# 04_iMX_8X_PWR.net
KiCad netlist of a schematic drawn in Altium Designer
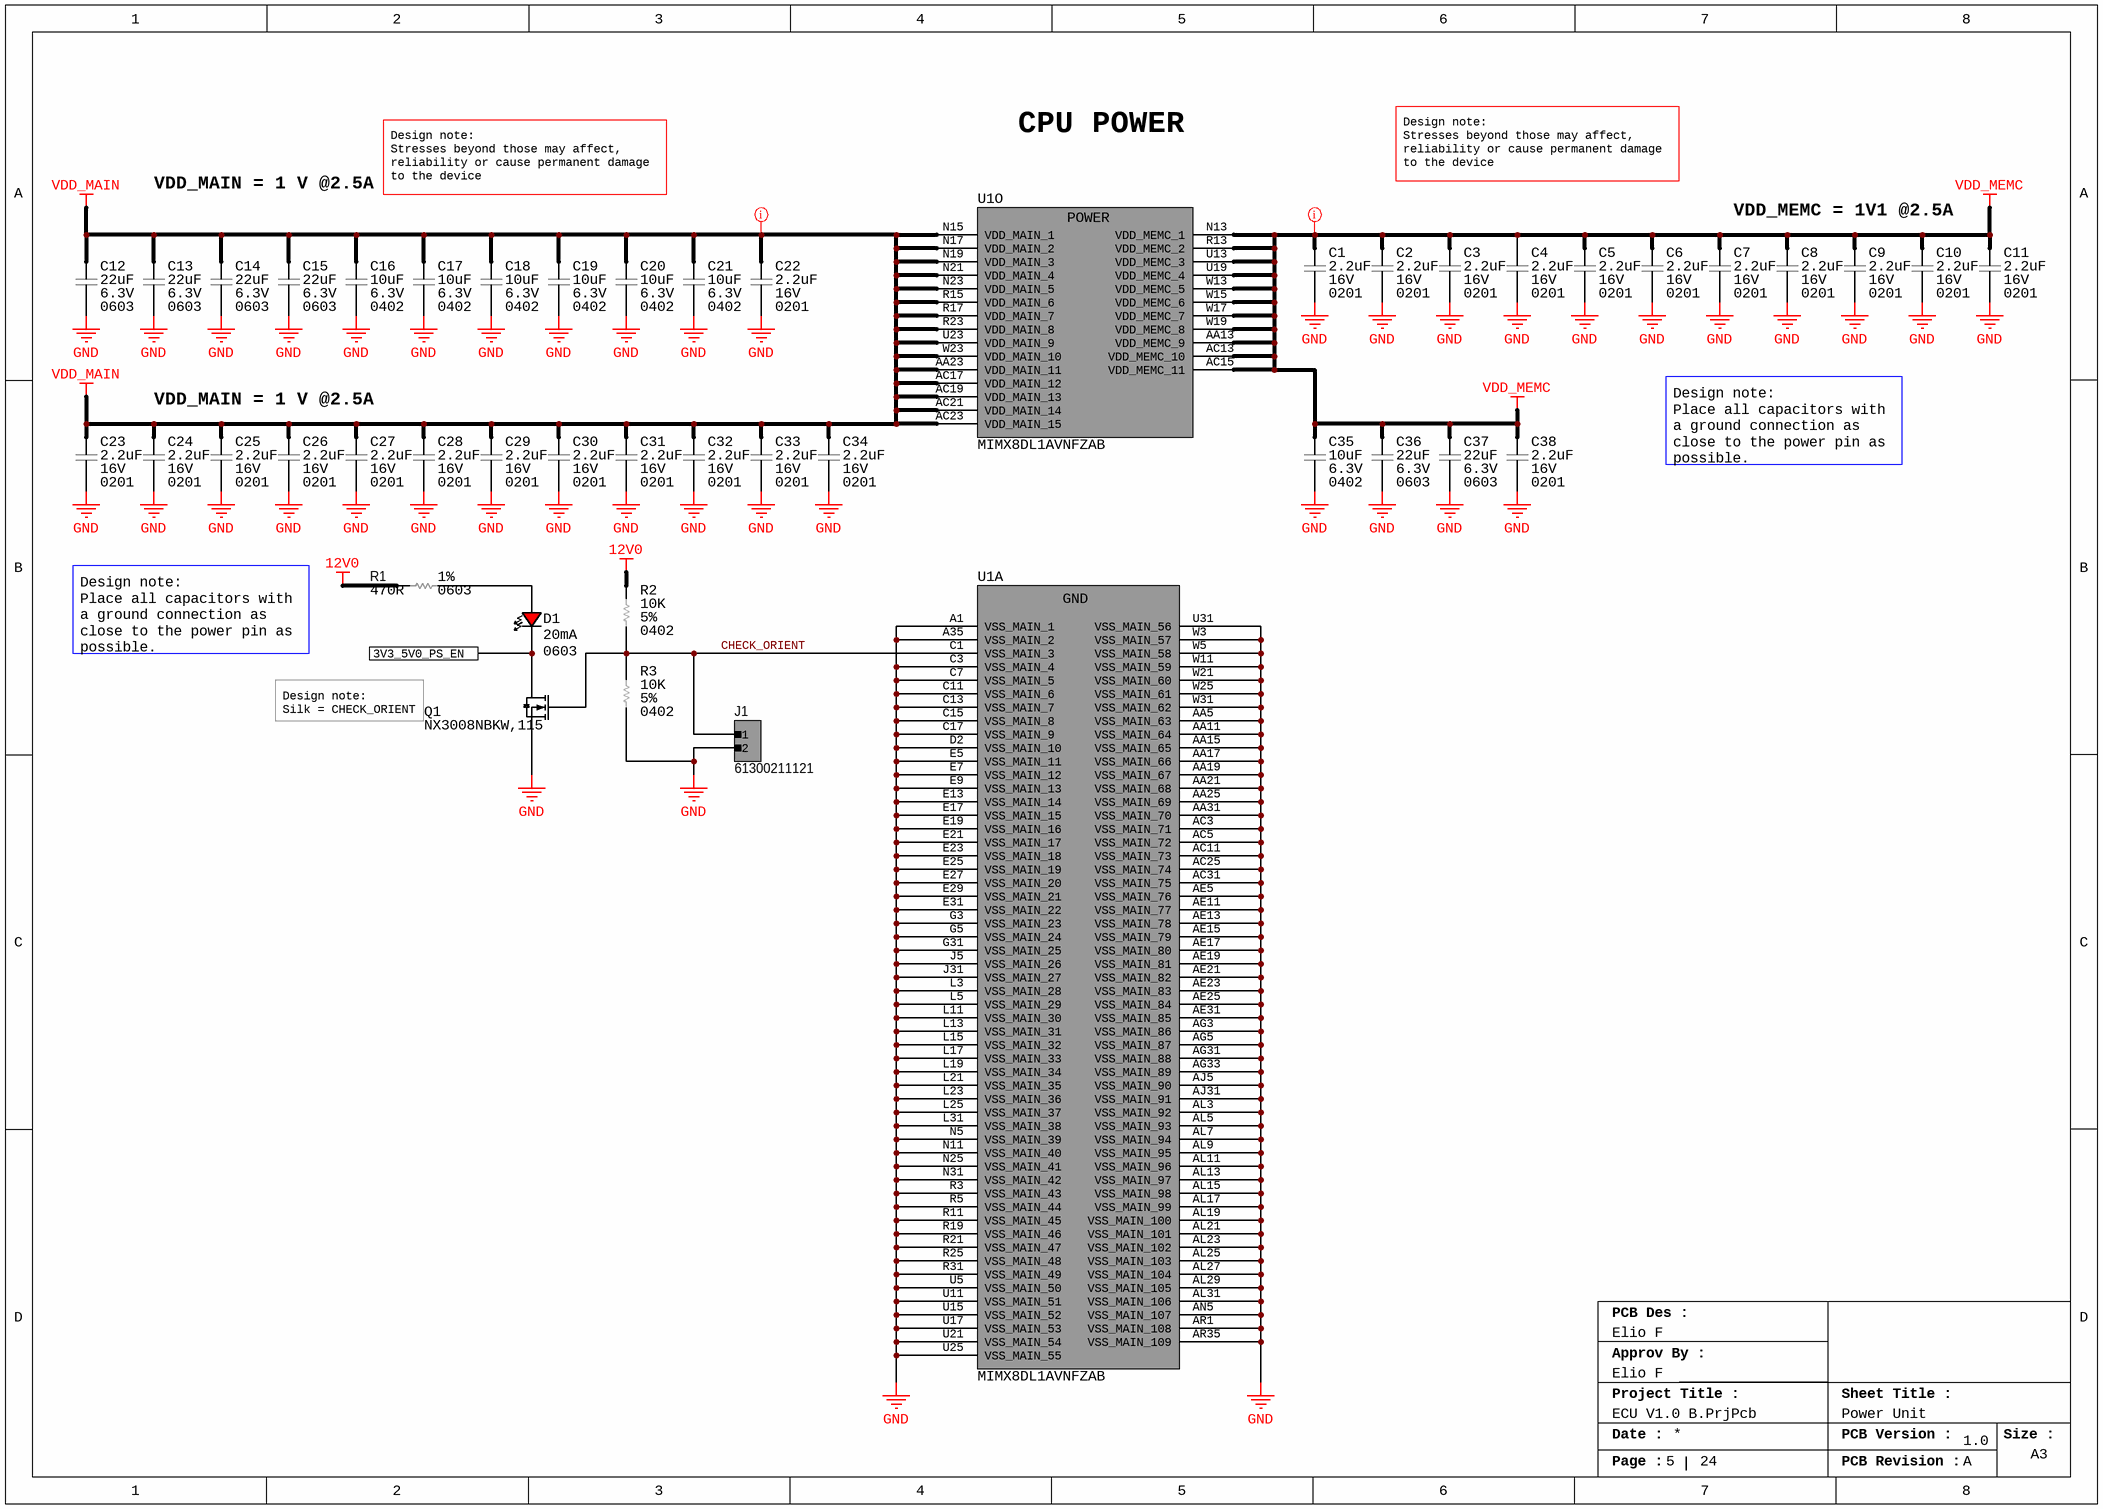
[diagram p0: 04_iMX 8X_PWR.SchDoc]

(export (version "E")
  (design (tool "Eeschema 10.0.6"))
  (components
    (comp (ref "C1")
      (value "GRM035R61C225ME01D")
      (footprint "CAP_0201_CAPC0603X03N")
      (description "General Up to 85C Reflow soldering")
      (fields
        (field (name "MANUFACTURER") "Murata")
        (field (name "TOLERANCE") "20%")
        (field (name "CAPACITANCE") "2.2uF")
        (field (name "VOLTAGE RATING") "16V")
        (field (name "CASE/PACKAGE") "0201")
      )
      (libsource (lib "Electronic Devices_LIB") (part "CAP_2.2uF_16V_X5R_0201"))
    )
    (comp (ref "C2")
      (value "GRM035R61C225ME01D")
      (footprint "CAP_0201_CAPC0603X03N")
      (description "General Up to 85C Reflow soldering")
      (fields
        (field (name "MANUFACTURER") "Murata")
        (field (name "TOLERANCE") "20%")
        (field (name "CAPACITANCE") "2.2uF")
        (field (name "VOLTAGE RATING") "16V")
        (field (name "CASE/PACKAGE") "0201")
      )
      (libsource (lib "Electronic Devices_LIB") (part "CAP_2.2uF_16V_X5R_0201"))
    )
    (comp (ref "C3")
      (value "GRM035R61C225ME01D")
      (footprint "CAP_0201_CAPC0603X03N")
      (description "General Up to 85C Reflow soldering")
      (fields
        (field (name "MANUFACTURER") "Murata")
        (field (name "TOLERANCE") "20%")
        (field (name "CAPACITANCE") "2.2uF")
        (field (name "VOLTAGE RATING") "16V")
        (field (name "CASE/PACKAGE") "0201")
      )
      (libsource (lib "Electronic Devices_LIB") (part "CAP_2.2uF_16V_X5R_0201"))
    )
    (comp (ref "C4")
      (value "GRM035R61C225ME01D")
      (footprint "CAP_0201_CAPC0603X03N")
      (description "General Up to 85C Reflow soldering")
      (fields
        (field (name "MANUFACTURER") "Murata")
        (field (name "TOLERANCE") "20%")
        (field (name "CAPACITANCE") "2.2uF")
        (field (name "VOLTAGE RATING") "16V")
        (field (name "CASE/PACKAGE") "0201")
      )
      (libsource (lib "Electronic Devices_LIB") (part "CAP_2.2uF_16V_X5R_0201"))
    )
    (comp (ref "C5")
      (value "GRM035R61C225ME01D")
      (footprint "CAP_0201_CAPC0603X03N")
      (description "General Up to 85C Reflow soldering")
      (fields
        (field (name "MANUFACTURER") "Murata")
        (field (name "TOLERANCE") "20%")
        (field (name "CAPACITANCE") "2.2uF")
        (field (name "VOLTAGE RATING") "16V")
        (field (name "CASE/PACKAGE") "0201")
      )
      (libsource (lib "Electronic Devices_LIB") (part "CAP_2.2uF_16V_X5R_0201"))
    )
    (comp (ref "C6")
      (value "GRM035R61C225ME01D")
      (footprint "CAP_0201_CAPC0603X03N")
      (description "General Up to 85C Reflow soldering")
      (fields
        (field (name "MANUFACTURER") "Murata")
        (field (name "TOLERANCE") "20%")
        (field (name "CAPACITANCE") "2.2uF")
        (field (name "VOLTAGE RATING") "16V")
        (field (name "CASE/PACKAGE") "0201")
      )
      (libsource (lib "Electronic Devices_LIB") (part "CAP_2.2uF_16V_X5R_0201"))
    )
    (comp (ref "C7")
      (value "GRM035R61C225ME01D")
      (footprint "CAP_0201_CAPC0603X03N")
      (description "General Up to 85C Reflow soldering")
      (fields
        (field (name "MANUFACTURER") "Murata")
        (field (name "TOLERANCE") "20%")
        (field (name "CAPACITANCE") "2.2uF")
        (field (name "VOLTAGE RATING") "16V")
        (field (name "CASE/PACKAGE") "0201")
      )
      (libsource (lib "Electronic Devices_LIB") (part "CAP_2.2uF_16V_X5R_0201"))
    )
    (comp (ref "C8")
      (value "GRM035R61C225ME01D")
      (footprint "CAP_0201_CAPC0603X03N")
      (description "General Up to 85C Reflow soldering")
      (fields
        (field (name "MANUFACTURER") "Murata")
        (field (name "TOLERANCE") "20%")
        (field (name "CAPACITANCE") "2.2uF")
        (field (name "VOLTAGE RATING") "16V")
        (field (name "CASE/PACKAGE") "0201")
      )
      (libsource (lib "Electronic Devices_LIB") (part "CAP_2.2uF_16V_X5R_0201"))
    )
    (comp (ref "C9")
      (value "GRM035R61C225ME01D")
      (footprint "CAP_0201_CAPC0603X03N")
      (description "General Up to 85C Reflow soldering")
      (fields
        (field (name "MANUFACTURER") "Murata")
        (field (name "TOLERANCE") "20%")
        (field (name "CAPACITANCE") "2.2uF")
        (field (name "VOLTAGE RATING") "16V")
        (field (name "CASE/PACKAGE") "0201")
      )
      (libsource (lib "Electronic Devices_LIB") (part "CAP_2.2uF_16V_X5R_0201"))
    )
    (comp (ref "C10")
      (value "GRM035R61C225ME01D")
      (footprint "CAP_0201_CAPC0603X03N")
      (description "General Up to 85C Reflow soldering")
      (fields
        (field (name "MANUFACTURER") "Murata")
        (field (name "TOLERANCE") "20%")
        (field (name "CAPACITANCE") "2.2uF")
        (field (name "VOLTAGE RATING") "16V")
        (field (name "CASE/PACKAGE") "0201")
      )
      (libsource (lib "Electronic Devices_LIB") (part "CAP_2.2uF_16V_X5R_0201"))
    )
    (comp (ref "C11")
      (value "GRM035R61C225ME01D")
      (footprint "CAP_0201_CAPC0603X03N")
      (description "General Up to 85C Reflow soldering")
      (fields
        (field (name "MANUFACTURER") "Murata")
        (field (name "TOLERANCE") "20%")
        (field (name "CAPACITANCE") "2.2uF")
        (field (name "VOLTAGE RATING") "16V")
        (field (name "CASE/PACKAGE") "0201")
      )
      (libsource (lib "Electronic Devices_LIB") (part "CAP_2.2uF_16V_X5R_0201"))
    )
    (comp (ref "C12")
      (value "GRM188R60J226MEA0D")
      (footprint "CAP_0603_CAPC1608X08N")
      (description "Multilayer Ceramic Capacitor, 22 uF, 6.3 V, ï¿½ 20%, X5R, 0603 [1608 Metric]")
      (fields
        (field (name "MANUFACTURER") "Murata")
        (field (name "TOLERANCE") "20%")
        (field (name "VOLTAGE RATING") "6.3V")
        (field (name "CAPACITANCE") "22uF")
        (field (name "CASE/PACKAGE") "0603")
      )
      (libsource (lib "Electronic Devices_LIB") (part "CAP_22uF_6.3V_X5R_0603"))
    )
    (comp (ref "C13")
      (value "GRM188R60J226MEA0D")
      (footprint "CAP_0603_CAPC1608X08N")
      (description "Multilayer Ceramic Capacitor, 22 uF, 6.3 V, ï¿½ 20%, X5R, 0603 [1608 Metric]")
      (fields
        (field (name "MANUFACTURER") "Murata")
        (field (name "TOLERANCE") "20%")
        (field (name "VOLTAGE RATING") "6.3V")
        (field (name "CAPACITANCE") "22uF")
        (field (name "CASE/PACKAGE") "0603")
      )
      (libsource (lib "Electronic Devices_LIB") (part "CAP_22uF_6.3V_X5R_0603"))
    )
    (comp (ref "C14")
      (value "GRM188R60J226MEA0D")
      (footprint "CAP_0603_CAPC1608X08N")
      (description "Multilayer Ceramic Capacitor, 22 uF, 6.3 V, ï¿½ 20%, X5R, 0603 [1608 Metric]")
      (fields
        (field (name "MANUFACTURER") "Murata")
        (field (name "TOLERANCE") "20%")
        (field (name "VOLTAGE RATING") "6.3V")
        (field (name "CAPACITANCE") "22uF")
        (field (name "CASE/PACKAGE") "0603")
      )
      (libsource (lib "Electronic Devices_LIB") (part "CAP_22uF_6.3V_X5R_0603"))
    )
    (comp (ref "C15")
      (value "GRM188R60J226MEA0D")
      (footprint "CAP_0603_CAPC1608X08N")
      (description "Multilayer Ceramic Capacitor, 22 uF, 6.3 V, ï¿½ 20%, X5R, 0603 [1608 Metric]")
      (fields
        (field (name "MANUFACTURER") "Murata")
        (field (name "TOLERANCE") "20%")
        (field (name "VOLTAGE RATING") "6.3V")
        (field (name "CAPACITANCE") "22uF")
        (field (name "CASE/PACKAGE") "0603")
      )
      (libsource (lib "Electronic Devices_LIB") (part "CAP_22uF_6.3V_X5R_0603"))
    )
    (comp (ref "C16")
      (value "CL05A106MQ5NUNC")
      (footprint "CAP_0402_CAPC1005X05N")
      (description "Cap Ceramic 10uF 6.3V X5R 20% SMD 0402 85C T/R")
      (fields
        (field (name "MANUFACTURER") "Samsung")
        (field (name "TOLERANCE") "20%")
        (field (name "CASE/PACKAGE") "0402")
        (field (name "CAPACITANCE") "10uF")
        (field (name "VOLTAGE RATING") "6.3V")
      )
      (libsource (lib "Electronic Devices_LIB") (part "CAP_10UF_6.3V_X5R_0402"))
    )
    (comp (ref "C17")
      (value "CL05A106MQ5NUNC")
      (footprint "CAP_0402_CAPC1005X05N")
      (description "Cap Ceramic 10uF 6.3V X5R 20% SMD 0402 85C T/R")
      (fields
        (field (name "MANUFACTURER") "Samsung")
        (field (name "TOLERANCE") "20%")
        (field (name "CASE/PACKAGE") "0402")
        (field (name "CAPACITANCE") "10uF")
        (field (name "VOLTAGE RATING") "6.3V")
      )
      (libsource (lib "Electronic Devices_LIB") (part "CAP_10UF_6.3V_X5R_0402"))
    )
    (comp (ref "C18")
      (value "CL05A106MQ5NUNC")
      (footprint "CAP_0402_CAPC1005X05N")
      (description "Cap Ceramic 10uF 6.3V X5R 20% SMD 0402 85C T/R")
      (fields
        (field (name "MANUFACTURER") "Samsung")
        (field (name "TOLERANCE") "20%")
        (field (name "CASE/PACKAGE") "0402")
        (field (name "CAPACITANCE") "10uF")
        (field (name "VOLTAGE RATING") "6.3V")
      )
      (libsource (lib "Electronic Devices_LIB") (part "CAP_10UF_6.3V_X5R_0402"))
    )
    (comp (ref "C19")
      (value "CL05A106MQ5NUNC")
      (footprint "CAP_0402_CAPC1005X05N")
      (description "Cap Ceramic 10uF 6.3V X5R 20% SMD 0402 85C T/R")
      (fields
        (field (name "MANUFACTURER") "Samsung")
        (field (name "TOLERANCE") "20%")
        (field (name "CASE/PACKAGE") "0402")
        (field (name "CAPACITANCE") "10uF")
        (field (name "VOLTAGE RATING") "6.3V")
      )
      (libsource (lib "Electronic Devices_LIB") (part "CAP_10UF_6.3V_X5R_0402"))
    )
    (comp (ref "C20")
      (value "CL05A106MQ5NUNC")
      (footprint "CAP_0402_CAPC1005X05N")
      (description "Cap Ceramic 10uF 6.3V X5R 20% SMD 0402 85C T/R")
      (fields
        (field (name "MANUFACTURER") "Samsung")
        (field (name "TOLERANCE") "20%")
        (field (name "CASE/PACKAGE") "0402")
        (field (name "CAPACITANCE") "10uF")
        (field (name "VOLTAGE RATING") "6.3V")
      )
      (libsource (lib "Electronic Devices_LIB") (part "CAP_10UF_6.3V_X5R_0402"))
    )
    (comp (ref "C21")
      (value "CL05A106MQ5NUNC")
      (footprint "CAP_0402_CAPC1005X05N")
      (description "Cap Ceramic 10uF 6.3V X5R 20% SMD 0402 85C T/R")
      (fields
        (field (name "MANUFACTURER") "Samsung")
        (field (name "TOLERANCE") "20%")
        (field (name "CASE/PACKAGE") "0402")
        (field (name "CAPACITANCE") "10uF")
        (field (name "VOLTAGE RATING") "6.3V")
      )
      (libsource (lib "Electronic Devices_LIB") (part "CAP_10UF_6.3V_X5R_0402"))
    )
    (comp (ref "C22")
      (value "GRM035R61C225ME01D")
      (footprint "CAP_0201_CAPC0603X03N")
      (description "General Up to 85C Reflow soldering")
      (fields
        (field (name "MANUFACTURER") "Murata")
        (field (name "TOLERANCE") "20%")
        (field (name "CAPACITANCE") "2.2uF")
        (field (name "VOLTAGE RATING") "16V")
        (field (name "CASE/PACKAGE") "0201")
      )
      (libsource (lib "Electronic Devices_LIB") (part "CAP_2.2uF_16V_X5R_0201"))
    )
    (comp (ref "C23")
      (value "GRM035R61C225ME01D")
      (footprint "CAP_0201_CAPC0603X03N")
      (description "General Up to 85C Reflow soldering")
      (fields
        (field (name "MANUFACTURER") "Murata")
        (field (name "TOLERANCE") "20%")
        (field (name "CAPACITANCE") "2.2uF")
        (field (name "VOLTAGE RATING") "16V")
        (field (name "CASE/PACKAGE") "0201")
      )
      (libsource (lib "Electronic Devices_LIB") (part "CAP_2.2uF_16V_X5R_0201"))
    )
    (comp (ref "C24")
      (value "GRM035R61C225ME01D")
      (footprint "CAP_0201_CAPC0603X03N")
      (description "General Up to 85C Reflow soldering")
      (fields
        (field (name "MANUFACTURER") "Murata")
        (field (name "TOLERANCE") "20%")
        (field (name "CAPACITANCE") "2.2uF")
        (field (name "VOLTAGE RATING") "16V")
        (field (name "CASE/PACKAGE") "0201")
      )
      (libsource (lib "Electronic Devices_LIB") (part "CAP_2.2uF_16V_X5R_0201"))
    )
    (comp (ref "C25")
      (value "GRM035R61C225ME01D")
      (footprint "CAP_0201_CAPC0603X03N")
      (description "General Up to 85C Reflow soldering")
      (fields
        (field (name "MANUFACTURER") "Murata")
        (field (name "TOLERANCE") "20%")
        (field (name "CAPACITANCE") "2.2uF")
        (field (name "VOLTAGE RATING") "16V")
        (field (name "CASE/PACKAGE") "0201")
      )
      (libsource (lib "Electronic Devices_LIB") (part "CAP_2.2uF_16V_X5R_0201"))
    )
    (comp (ref "C26")
      (value "GRM035R61C225ME01D")
      (footprint "CAP_0201_CAPC0603X03N")
      (description "General Up to 85C Reflow soldering")
      (fields
        (field (name "MANUFACTURER") "Murata")
        (field (name "TOLERANCE") "20%")
        (field (name "CAPACITANCE") "2.2uF")
        (field (name "VOLTAGE RATING") "16V")
        (field (name "CASE/PACKAGE") "0201")
      )
      (libsource (lib "Electronic Devices_LIB") (part "CAP_2.2uF_16V_X5R_0201"))
    )
    (comp (ref "C27")
      (value "GRM035R61C225ME01D")
      (footprint "CAP_0201_CAPC0603X03N")
      (description "General Up to 85C Reflow soldering")
      (fields
        (field (name "MANUFACTURER") "Murata")
        (field (name "TOLERANCE") "20%")
        (field (name "CAPACITANCE") "2.2uF")
        (field (name "VOLTAGE RATING") "16V")
        (field (name "CASE/PACKAGE") "0201")
      )
      (libsource (lib "Electronic Devices_LIB") (part "CAP_2.2uF_16V_X5R_0201"))
    )
    (comp (ref "C28")
      (value "GRM035R61C225ME01D")
      (footprint "CAP_0201_CAPC0603X03N")
      (description "General Up to 85C Reflow soldering")
      (fields
        (field (name "MANUFACTURER") "Murata")
        (field (name "TOLERANCE") "20%")
        (field (name "CAPACITANCE") "2.2uF")
        (field (name "VOLTAGE RATING") "16V")
        (field (name "CASE/PACKAGE") "0201")
      )
      (libsource (lib "Electronic Devices_LIB") (part "CAP_2.2uF_16V_X5R_0201"))
    )
    (comp (ref "C29")
      (value "GRM035R61C225ME01D")
      (footprint "CAP_0201_CAPC0603X03N")
      (description "General Up to 85C Reflow soldering")
      (fields
        (field (name "MANUFACTURER") "Murata")
        (field (name "TOLERANCE") "20%")
        (field (name "CAPACITANCE") "2.2uF")
        (field (name "VOLTAGE RATING") "16V")
        (field (name "CASE/PACKAGE") "0201")
      )
      (libsource (lib "Electronic Devices_LIB") (part "CAP_2.2uF_16V_X5R_0201"))
    )
    (comp (ref "C30")
      (value "GRM035R61C225ME01D")
      (footprint "CAP_0201_CAPC0603X03N")
      (description "General Up to 85C Reflow soldering")
      (fields
        (field (name "MANUFACTURER") "Murata")
        (field (name "TOLERANCE") "20%")
        (field (name "CAPACITANCE") "2.2uF")
        (field (name "VOLTAGE RATING") "16V")
        (field (name "CASE/PACKAGE") "0201")
      )
      (libsource (lib "Electronic Devices_LIB") (part "CAP_2.2uF_16V_X5R_0201"))
    )
    (comp (ref "C31")
      (value "GRM035R61C225ME01D")
      (footprint "CAP_0201_CAPC0603X03N")
      (description "General Up to 85C Reflow soldering")
      (fields
        (field (name "MANUFACTURER") "Murata")
        (field (name "TOLERANCE") "20%")
        (field (name "CAPACITANCE") "2.2uF")
        (field (name "VOLTAGE RATING") "16V")
        (field (name "CASE/PACKAGE") "0201")
      )
      (libsource (lib "Electronic Devices_LIB") (part "CAP_2.2uF_16V_X5R_0201"))
    )
    (comp (ref "C32")
      (value "GRM035R61C225ME01D")
      (footprint "CAP_0201_CAPC0603X03N")
      (description "General Up to 85C Reflow soldering")
      (fields
        (field (name "MANUFACTURER") "Murata")
        (field (name "TOLERANCE") "20%")
        (field (name "CAPACITANCE") "2.2uF")
        (field (name "VOLTAGE RATING") "16V")
        (field (name "CASE/PACKAGE") "0201")
      )
      (libsource (lib "Electronic Devices_LIB") (part "CAP_2.2uF_16V_X5R_0201"))
    )
    (comp (ref "C33")
      (value "GRM035R61C225ME01D")
      (footprint "CAP_0201_CAPC0603X03N")
      (description "General Up to 85C Reflow soldering")
      (fields
        (field (name "MANUFACTURER") "Murata")
        (field (name "TOLERANCE") "20%")
        (field (name "CAPACITANCE") "2.2uF")
        (field (name "VOLTAGE RATING") "16V")
        (field (name "CASE/PACKAGE") "0201")
      )
      (libsource (lib "Electronic Devices_LIB") (part "CAP_2.2uF_16V_X5R_0201"))
    )
    (comp (ref "C34")
      (value "GRM035R61C225ME01D")
      (footprint "CAP_0201_CAPC0603X03N")
      (description "General Up to 85C Reflow soldering")
      (fields
        (field (name "MANUFACTURER") "Murata")
        (field (name "TOLERANCE") "20%")
        (field (name "CAPACITANCE") "2.2uF")
        (field (name "VOLTAGE RATING") "16V")
        (field (name "CASE/PACKAGE") "0201")
      )
      (libsource (lib "Electronic Devices_LIB") (part "CAP_2.2uF_16V_X5R_0201"))
    )
    (comp (ref "C35")
      (value "CL05A106MQ5NUNC")
      (footprint "CAP_0402_CAPC1005X05N")
      (description "Cap Ceramic 10uF 6.3V X5R 20% SMD 0402 85C T/R")
      (fields
        (field (name "MANUFACTURER") "Samsung")
        (field (name "TOLERANCE") "20%")
        (field (name "CASE/PACKAGE") "0402")
        (field (name "CAPACITANCE") "10uF")
        (field (name "VOLTAGE RATING") "6.3V")
      )
      (libsource (lib "Electronic Devices_LIB") (part "CAP_10UF_6.3V_X5R_0402"))
    )
    (comp (ref "C36")
      (value "GRM188R60J226MEA0D")
      (footprint "CAP_0603_CAPC1608X08N")
      (description "Multilayer Ceramic Capacitor, 22 uF, 6.3 V, ï¿½ 20%, X5R, 0603 [1608 Metric]")
      (fields
        (field (name "MANUFACTURER") "Murata")
        (field (name "TOLERANCE") "20%")
        (field (name "VOLTAGE RATING") "6.3V")
        (field (name "CAPACITANCE") "22uF")
        (field (name "CASE/PACKAGE") "0603")
      )
      (libsource (lib "Electronic Devices_LIB") (part "CAP_22uF_6.3V_X5R_0603"))
    )
    (comp (ref "C37")
      (value "GRM188R60J226MEA0D")
      (footprint "CAP_0603_CAPC1608X08N")
      (description "Multilayer Ceramic Capacitor, 22 uF, 6.3 V, ï¿½ 20%, X5R, 0603 [1608 Metric]")
      (fields
        (field (name "MANUFACTURER") "Murata")
        (field (name "TOLERANCE") "20%")
        (field (name "VOLTAGE RATING") "6.3V")
        (field (name "CAPACITANCE") "22uF")
        (field (name "CASE/PACKAGE") "0603")
      )
      (libsource (lib "Electronic Devices_LIB") (part "CAP_22uF_6.3V_X5R_0603"))
    )
    (comp (ref "C38")
      (value "GRM035R61C225ME01D")
      (footprint "CAP_0201_CAPC0603X03N")
      (description "General Up to 85C Reflow soldering")
      (fields
        (field (name "MANUFACTURER") "Murata")
        (field (name "TOLERANCE") "20%")
        (field (name "CAPACITANCE") "2.2uF")
        (field (name "VOLTAGE RATING") "16V")
        (field (name "CASE/PACKAGE") "0201")
      )
      (libsource (lib "Electronic Devices_LIB") (part "CAP_2.2uF_16V_X5R_0201"))
    )
    (comp (ref "D1")
      (value "LTST-C190KRKT")
      (footprint "LED_0603-RED-0.75mm")
      (description "LED,  LTST-C190KRKT")
      (fields
        (field (name "MANUFACTURER") "Vishay Lite-On")
        (field (name "TEST CURRENT") "20mA")
        (field (name "CASE/PACKAGE") "0603")
      )
      (libsource (lib "Electronic Devices_LIB") (part "LED_DIO_RED_20mA_0603"))
    )
    (comp (ref "J1")
      (value "61300211121")
      (footprint "HEADER_MALE_HDRV2W110P0X254_1X2_508X254X854P")
      (description "THT Vertical Pin Header WR-PHD, Pitch 2.54 mm, Single Row, 2 pins")
      (fields (field (name "MANUFACTURER") "Wurth Electronics"))
      (libsource (lib "Electronic Devices_LIB") (part "CONN_HEADER_MALE_2P_2.54_61300211121"))
    )
    (comp (ref "Q1")
      (value "NX3008NBKW,115")
      (footprint "TRANS_FET_SOT65P210X110-3N")
      (description "Trans MOSFET N-CH 30V 0.35A Automotive 3-Pin SC-70 T/R")
      (fields (field (name "MANUFACTURER") "Nexperia"))
      (libsource (lib "Electronic Devices_LIB") (part "TRANS_FET_CH_N_NX3008NBKW,115"))
    )
    (comp (ref "R1")
      (value "RC0603FR-07470RL")
      (footprint "RES_0603_RESC1608X04N")
      (description "SMD Chip Resistor, 470 Ohm, ± 1%, 100 mW, 0603 [1608 Metric], Thick Film, General Purpose")
      (fields
        (field (name "MANUFACTURER") "Yageo")
        (field (name "TOLERANCE") "1%")
        (field (name "RESISTANCE") "470R")
        (field (name "CASE/PACKAGE") "0603")
      )
      (libsource (lib "Electronic Devices_LIB") (part "RES_470R_1%_100mW_0603"))
    )
    (comp (ref "R2")
      (value "ERJ-2GEJ103X")
      (footprint "RES_0402_RESC1005X04N")
      (description "Res Thick Film 0402 10K Ohm 5% 1/10W ±200ppm/°C Molded SMD Punched Carrier T/R")
      (fields
        (field (name "MANUFACTURER") "Panasonic")
        (field (name "TOLERANCE") "5%")
        (field (name "RESISTANCE") "10K")
        (field (name "CASE/PACKAGE") "0402")
      )
      (libsource (lib "Electronic Devices_LIB") (part "RES_10K_5%_100mW_0402"))
    )
    (comp (ref "R3")
      (value "ERJ-2GEJ103X")
      (footprint "RES_0402_RESC1005X04N")
      (description "Res Thick Film 0402 10K Ohm 5% 1/10W ±200ppm/°C Molded SMD Punched Carrier T/R")
      (fields
        (field (name "MANUFACTURER") "Panasonic")
        (field (name "TOLERANCE") "5%")
        (field (name "RESISTANCE") "10K")
        (field (name "CASE/PACKAGE") "0402")
      )
      (libsource (lib "Electronic Devices_LIB") (part "RES_10K_5%_100mW_0402"))
    )
    (comp (ref "U1")
      (value "MIMX8DL1AVNFZAB")
      (footprint "MIMX8DL1AVNFZAB")
      (description "I.MX8 Dxl 15SQ / Tray Rohs Compliant: Yes")
      (fields (field (name "MANUFACTURER") "NXP Semiconductors"))
      (libsource (lib "Electronic Devices_LIB") (part "IC_MPU_ARM_1.2GHz_MIMX8DL1AVNFZAB"))
    )
  )
  (nets
    (net (code "1") (name "/3V3_5V0_PS_EN") (class "Default")
      (node (ref "D1") (pin "1") (pinfunction "C_1") (pintype "passive"))
      (node (ref "Q1") (pin "D") (pinfunction "D_D") (pintype "passive"))
    )
    (net (code "2") (name "/CHECK_ORIENT") (class "Default")
      (node (ref "J1") (pin "1") (pinfunction "1_1") (pintype "passive"))
      (node (ref "Q1") (pin "G") (pinfunction "G_G") (pintype "passive"))
      (node (ref "R2") (pin "2") (pinfunction "2_2") (pintype "passive"))
      (node (ref "R3") (pin "1") (pinfunction "1_1") (pintype "passive"))
      (node (ref "U1") (pin "C1") (pinfunction "VSS_MAIN_3_C1") (pintype "passive"))
    )
    (net (code "3") (name "12V0") (class "Default")
      (node (ref "R1") (pin "1") (pinfunction "1_1") (pintype "passive"))
      (node (ref "R2") (pin "1") (pinfunction "1_1") (pintype "passive"))
    )
    (net (code "4") (name "GND") (class "Default")
      (node (ref "C1") (pin "1") (pinfunction "1_1") (pintype "passive"))
      (node (ref "C10") (pin "1") (pinfunction "1_1") (pintype "passive"))
      (node (ref "C11") (pin "1") (pinfunction "1_1") (pintype "passive"))
      (node (ref "C12") (pin "1") (pinfunction "1_1") (pintype "passive"))
      (node (ref "C13") (pin "1") (pinfunction "1_1") (pintype "passive"))
      (node (ref "C14") (pin "1") (pinfunction "1_1") (pintype "passive"))
      (node (ref "C15") (pin "1") (pinfunction "1_1") (pintype "passive"))
      (node (ref "C16") (pin "1") (pinfunction "1_1") (pintype "passive"))
      (node (ref "C17") (pin "1") (pinfunction "1_1") (pintype "passive"))
      (node (ref "C18") (pin "1") (pinfunction "1_1") (pintype "passive"))
      (node (ref "C19") (pin "1") (pinfunction "1_1") (pintype "passive"))
      (node (ref "C2") (pin "1") (pinfunction "1_1") (pintype "passive"))
      (node (ref "C20") (pin "1") (pinfunction "1_1") (pintype "passive"))
      (node (ref "C21") (pin "1") (pinfunction "1_1") (pintype "passive"))
      (node (ref "C22") (pin "1") (pinfunction "1_1") (pintype "passive"))
      (node (ref "C23") (pin "1") (pinfunction "1_1") (pintype "passive"))
      (node (ref "C24") (pin "1") (pinfunction "1_1") (pintype "passive"))
      (node (ref "C25") (pin "1") (pinfunction "1_1") (pintype "passive"))
      (node (ref "C26") (pin "1") (pinfunction "1_1") (pintype "passive"))
      (node (ref "C27") (pin "1") (pinfunction "1_1") (pintype "passive"))
      (node (ref "C28") (pin "1") (pinfunction "1_1") (pintype "passive"))
      (node (ref "C29") (pin "1") (pinfunction "1_1") (pintype "passive"))
      (node (ref "C3") (pin "1") (pinfunction "1_1") (pintype "passive"))
      (node (ref "C30") (pin "1") (pinfunction "1_1") (pintype "passive"))
      (node (ref "C31") (pin "1") (pinfunction "1_1") (pintype "passive"))
      (node (ref "C32") (pin "1") (pinfunction "1_1") (pintype "passive"))
      (node (ref "C33") (pin "1") (pinfunction "1_1") (pintype "passive"))
      (node (ref "C34") (pin "1") (pinfunction "1_1") (pintype "passive"))
      (node (ref "C35") (pin "1") (pinfunction "1_1") (pintype "passive"))
      (node (ref "C36") (pin "1") (pinfunction "1_1") (pintype "passive"))
      (node (ref "C37") (pin "1") (pinfunction "1_1") (pintype "passive"))
      (node (ref "C38") (pin "1") (pinfunction "1_1") (pintype "passive"))
      (node (ref "C4") (pin "1") (pinfunction "1_1") (pintype "passive"))
      (node (ref "C5") (pin "1") (pinfunction "1_1") (pintype "passive"))
      (node (ref "C6") (pin "1") (pinfunction "1_1") (pintype "passive"))
      (node (ref "C7") (pin "1") (pinfunction "1_1") (pintype "passive"))
      (node (ref "C8") (pin "1") (pinfunction "1_1") (pintype "passive"))
      (node (ref "C9") (pin "1") (pinfunction "1_1") (pintype "passive"))
      (node (ref "J1") (pin "2") (pinfunction "2_2") (pintype "passive"))
      (node (ref "Q1") (pin "S") (pinfunction "S_S") (pintype "passive"))
      (node (ref "R3") (pin "2") (pinfunction "2_2") (pintype "passive"))
      (node (ref "U1") (pin "A1") (pinfunction "VSS_MAIN_1_A1") (pintype "passive"))
      (node (ref "U1") (pin "A35") (pinfunction "VSS_MAIN_2_A35") (pintype "passive"))
      (node (ref "U1") (pin "AA11") (pinfunction "VSS_MAIN_64_AA11") (pintype "passive"))
      (node (ref "U1") (pin "AA15") (pinfunction "VSS_MAIN_65_AA15") (pintype "passive"))
      (node (ref "U1") (pin "AA17") (pinfunction "VSS_MAIN_66_AA17") (pintype "passive"))
      (node (ref "U1") (pin "AA19") (pinfunction "VSS_MAIN_67_AA19") (pintype "passive"))
      (node (ref "U1") (pin "AA21") (pinfunction "VSS_MAIN_68_AA21") (pintype "passive"))
      (node (ref "U1") (pin "AA25") (pinfunction "VSS_MAIN_69_AA25") (pintype "passive"))
      (node (ref "U1") (pin "AA31") (pinfunction "VSS_MAIN_70_AA31") (pintype "passive"))
      (node (ref "U1") (pin "AA5") (pinfunction "VSS_MAIN_63_AA5") (pintype "passive"))
      (node (ref "U1") (pin "AC11") (pinfunction "VSS_MAIN_73_AC11") (pintype "passive"))
      (node (ref "U1") (pin "AC25") (pinfunction "VSS_MAIN_74_AC25") (pintype "passive"))
      (node (ref "U1") (pin "AC3") (pinfunction "VSS_MAIN_71_AC3") (pintype "passive"))
      (node (ref "U1") (pin "AC31") (pinfunction "VSS_MAIN_75_AC31") (pintype "passive"))
      (node (ref "U1") (pin "AC5") (pinfunction "VSS_MAIN_72_AC5") (pintype "passive"))
      (node (ref "U1") (pin "AE11") (pinfunction "VSS_MAIN_77_AE11") (pintype "passive"))
      (node (ref "U1") (pin "AE13") (pinfunction "VSS_MAIN_78_AE13") (pintype "passive"))
      (node (ref "U1") (pin "AE15") (pinfunction "VSS_MAIN_79_AE15") (pintype "passive"))
      (node (ref "U1") (pin "AE17") (pinfunction "VSS_MAIN_80_AE17") (pintype "passive"))
      (node (ref "U1") (pin "AE19") (pinfunction "VSS_MAIN_81_AE19") (pintype "passive"))
      (node (ref "U1") (pin "AE21") (pinfunction "VSS_MAIN_82_AE21") (pintype "passive"))
      (node (ref "U1") (pin "AE23") (pinfunction "VSS_MAIN_83_AE23") (pintype "passive"))
      (node (ref "U1") (pin "AE25") (pinfunction "VSS_MAIN_84_AE25") (pintype "passive"))
      (node (ref "U1") (pin "AE31") (pinfunction "VSS_MAIN_85_AE31") (pintype "passive"))
      (node (ref "U1") (pin "AE5") (pinfunction "VSS_MAIN_76_AE5") (pintype "passive"))
      (node (ref "U1") (pin "AG3") (pinfunction "VSS_MAIN_86_AG3") (pintype "passive"))
      (node (ref "U1") (pin "AG31") (pinfunction "VSS_MAIN_88_AG31") (pintype "passive"))
      (node (ref "U1") (pin "AG33") (pinfunction "VSS_MAIN_89_AG33") (pintype "passive"))
      (node (ref "U1") (pin "AG5") (pinfunction "VSS_MAIN_87_AG5") (pintype "passive"))
      (node (ref "U1") (pin "AJ31") (pinfunction "VSS_MAIN_91_AJ31") (pintype "passive"))
      (node (ref "U1") (pin "AJ5") (pinfunction "VSS_MAIN_90_AJ5") (pintype "passive"))
      (node (ref "U1") (pin "AL11") (pinfunction "VSS_MAIN_96_AL11") (pintype "passive"))
      (node (ref "U1") (pin "AL13") (pinfunction "VSS_MAIN_97_AL13") (pintype "passive"))
      (node (ref "U1") (pin "AL15") (pinfunction "VSS_MAIN_98_AL15") (pintype "passive"))
      (node (ref "U1") (pin "AL17") (pinfunction "VSS_MAIN_99_AL17") (pintype "passive"))
      (node (ref "U1") (pin "AL19") (pinfunction "VSS_MAIN_100_AL19") (pintype "passive"))
      (node (ref "U1") (pin "AL21") (pinfunction "VSS_MAIN_101_AL21") (pintype "passive"))
      (node (ref "U1") (pin "AL23") (pinfunction "VSS_MAIN_102_AL23") (pintype "passive"))
      (node (ref "U1") (pin "AL25") (pinfunction "VSS_MAIN_103_AL25") (pintype "passive"))
      (node (ref "U1") (pin "AL27") (pinfunction "VSS_MAIN_104_AL27") (pintype "passive"))
      (node (ref "U1") (pin "AL29") (pinfunction "VSS_MAIN_105_AL29") (pintype "passive"))
      (node (ref "U1") (pin "AL3") (pinfunction "VSS_MAIN_92_AL3") (pintype "passive"))
      (node (ref "U1") (pin "AL31") (pinfunction "VSS_MAIN_106_AL31") (pintype "passive"))
      (node (ref "U1") (pin "AL5") (pinfunction "VSS_MAIN_93_AL5") (pintype "passive"))
      (node (ref "U1") (pin "AL7") (pinfunction "VSS_MAIN_94_AL7") (pintype "passive"))
      (node (ref "U1") (pin "AL9") (pinfunction "VSS_MAIN_95_AL9") (pintype "passive"))
      (node (ref "U1") (pin "AN5") (pinfunction "VSS_MAIN_107_AN5") (pintype "passive"))
      (node (ref "U1") (pin "AR1") (pinfunction "VSS_MAIN_108_AR1") (pintype "passive"))
      (node (ref "U1") (pin "AR35") (pinfunction "VSS_MAIN_109_AR35") (pintype "passive"))
      (node (ref "U1") (pin "C11") (pinfunction "VSS_MAIN_6_C11") (pintype "passive"))
      (node (ref "U1") (pin "C13") (pinfunction "VSS_MAIN_7_C13") (pintype "passive"))
      (node (ref "U1") (pin "C15") (pinfunction "VSS_MAIN_8_C15") (pintype "passive"))
      (node (ref "U1") (pin "C17") (pinfunction "VSS_MAIN_9_C17") (pintype "passive"))
      (node (ref "U1") (pin "C3") (pinfunction "VSS_MAIN_4_C3") (pintype "passive"))
      (node (ref "U1") (pin "C7") (pinfunction "VSS_MAIN_5_C7") (pintype "passive"))
      (node (ref "U1") (pin "D2") (pinfunction "VSS_MAIN_10_D2") (pintype "passive"))
      (node (ref "U1") (pin "E13") (pinfunction "VSS_MAIN_14_E13") (pintype "passive"))
      (node (ref "U1") (pin "E17") (pinfunction "VSS_MAIN_15_E17") (pintype "passive"))
      (node (ref "U1") (pin "E19") (pinfunction "VSS_MAIN_16_E19") (pintype "passive"))
      (node (ref "U1") (pin "E21") (pinfunction "VSS_MAIN_17_E21") (pintype "passive"))
      (node (ref "U1") (pin "E23") (pinfunction "VSS_MAIN_18_E23") (pintype "passive"))
      (node (ref "U1") (pin "E25") (pinfunction "VSS_MAIN_19_E25") (pintype "passive"))
      (node (ref "U1") (pin "E27") (pinfunction "VSS_MAIN_20_E27") (pintype "passive"))
      (node (ref "U1") (pin "E29") (pinfunction "VSS_MAIN_21_E29") (pintype "passive"))
      (node (ref "U1") (pin "E31") (pinfunction "VSS_MAIN_22_E31") (pintype "passive"))
      (node (ref "U1") (pin "E5") (pinfunction "VSS_MAIN_11_E5") (pintype "passive"))
      (node (ref "U1") (pin "E7") (pinfunction "VSS_MAIN_12_E7") (pintype "passive"))
      (node (ref "U1") (pin "E9") (pinfunction "VSS_MAIN_13_E9") (pintype "passive"))
      (node (ref "U1") (pin "G3") (pinfunction "VSS_MAIN_23_G3") (pintype "passive"))
      (node (ref "U1") (pin "G31") (pinfunction "VSS_MAIN_25_G31") (pintype "passive"))
      (node (ref "U1") (pin "G5") (pinfunction "VSS_MAIN_24_G5") (pintype "passive"))
      (node (ref "U1") (pin "J31") (pinfunction "VSS_MAIN_27_J31") (pintype "passive"))
      (node (ref "U1") (pin "J5") (pinfunction "VSS_MAIN_26_J5") (pintype "passive"))
      (node (ref "U1") (pin "L11") (pinfunction "VSS_MAIN_30_L11") (pintype "passive"))
      (node (ref "U1") (pin "L13") (pinfunction "VSS_MAIN_31_L13") (pintype "passive"))
      (node (ref "U1") (pin "L15") (pinfunction "VSS_MAIN_32_L15") (pintype "passive"))
      (node (ref "U1") (pin "L17") (pinfunction "VSS_MAIN_33_L17") (pintype "passive"))
      (node (ref "U1") (pin "L19") (pinfunction "VSS_MAIN_34_L19") (pintype "passive"))
      (node (ref "U1") (pin "L21") (pinfunction "VSS_MAIN_35_L21") (pintype "passive"))
      (node (ref "U1") (pin "L23") (pinfunction "VSS_MAIN_36_L23") (pintype "passive"))
      (node (ref "U1") (pin "L25") (pinfunction "VSS_MAIN_37_L25") (pintype "passive"))
      (node (ref "U1") (pin "L3") (pinfunction "VSS_MAIN_28_L3") (pintype "passive"))
      (node (ref "U1") (pin "L31") (pinfunction "VSS_MAIN_38_L31") (pintype "passive"))
      (node (ref "U1") (pin "L5") (pinfunction "VSS_MAIN_29_L5") (pintype "passive"))
      (node (ref "U1") (pin "N11") (pinfunction "VSS_MAIN_40_N11") (pintype "passive"))
      (node (ref "U1") (pin "N25") (pinfunction "VSS_MAIN_41_N25") (pintype "passive"))
      (node (ref "U1") (pin "N31") (pinfunction "VSS_MAIN_42_N31") (pintype "passive"))
      (node (ref "U1") (pin "N5") (pinfunction "VSS_MAIN_39_N5") (pintype "passive"))
      (node (ref "U1") (pin "R11") (pinfunction "VSS_MAIN_45_R11") (pintype "passive"))
      (node (ref "U1") (pin "R19") (pinfunction "VSS_MAIN_46_R19") (pintype "passive"))
      (node (ref "U1") (pin "R21") (pinfunction "VSS_MAIN_47_R21") (pintype "passive"))
      (node (ref "U1") (pin "R25") (pinfunction "VSS_MAIN_48_R25") (pintype "passive"))
      (node (ref "U1") (pin "R3") (pinfunction "VSS_MAIN_43_R3") (pintype "passive"))
      (node (ref "U1") (pin "R31") (pinfunction "VSS_MAIN_49_R31") (pintype "passive"))
      (node (ref "U1") (pin "R5") (pinfunction "VSS_MAIN_44_R5") (pintype "passive"))
      (node (ref "U1") (pin "U11") (pinfunction "VSS_MAIN_51_U11") (pintype "passive"))
      (node (ref "U1") (pin "U15") (pinfunction "VSS_MAIN_52_U15") (pintype "passive"))
      (node (ref "U1") (pin "U17") (pinfunction "VSS_MAIN_53_U17") (pintype "passive"))
      (node (ref "U1") (pin "U21") (pinfunction "VSS_MAIN_54_U21") (pintype "passive"))
      (node (ref "U1") (pin "U25") (pinfunction "VSS_MAIN_55_U25") (pintype "passive"))
      (node (ref "U1") (pin "U31") (pinfunction "VSS_MAIN_56_U31") (pintype "passive"))
      (node (ref "U1") (pin "U5") (pinfunction "VSS_MAIN_50_U5") (pintype "passive"))
      (node (ref "U1") (pin "W11") (pinfunction "VSS_MAIN_59_W11") (pintype "passive"))
      (node (ref "U1") (pin "W21") (pinfunction "VSS_MAIN_60_W21") (pintype "passive"))
      (node (ref "U1") (pin "W25") (pinfunction "VSS_MAIN_61_W25") (pintype "passive"))
      (node (ref "U1") (pin "W3") (pinfunction "VSS_MAIN_57_W3") (pintype "passive"))
      (node (ref "U1") (pin "W31") (pinfunction "VSS_MAIN_62_W31") (pintype "passive"))
      (node (ref "U1") (pin "W5") (pinfunction "VSS_MAIN_58_W5") (pintype "passive"))
    )
    (net (code "5") (name "Net-(D1-A)") (class "Default")
      (node (ref "D1") (pin "2") (pinfunction "A_2") (pintype "passive"))
      (node (ref "R1") (pin "2") (pinfunction "2_2") (pintype "passive"))
    )
    (net (code "6") (name "VDD_MAIN") (class "Default")
      (node (ref "C12") (pin "2") (pinfunction "2_2") (pintype "passive"))
      (node (ref "C13") (pin "2") (pinfunction "2_2") (pintype "passive"))
      (node (ref "C14") (pin "2") (pinfunction "2_2") (pintype "passive"))
      (node (ref "C15") (pin "2") (pinfunction "2_2") (pintype "passive"))
      (node (ref "C16") (pin "2") (pinfunction "2_2") (pintype "passive"))
      (node (ref "C17") (pin "2") (pinfunction "2_2") (pintype "passive"))
      (node (ref "C18") (pin "2") (pinfunction "2_2") (pintype "passive"))
      (node (ref "C19") (pin "2") (pinfunction "2_2") (pintype "passive"))
      (node (ref "C20") (pin "2") (pinfunction "2_2") (pintype "passive"))
      (node (ref "C21") (pin "2") (pinfunction "2_2") (pintype "passive"))
      (node (ref "C22") (pin "2") (pinfunction "2_2") (pintype "passive"))
      (node (ref "C23") (pin "2") (pinfunction "2_2") (pintype "passive"))
      (node (ref "C24") (pin "2") (pinfunction "2_2") (pintype "passive"))
      (node (ref "C25") (pin "2") (pinfunction "2_2") (pintype "passive"))
      (node (ref "C26") (pin "2") (pinfunction "2_2") (pintype "passive"))
      (node (ref "C27") (pin "2") (pinfunction "2_2") (pintype "passive"))
      (node (ref "C28") (pin "2") (pinfunction "2_2") (pintype "passive"))
      (node (ref "C29") (pin "2") (pinfunction "2_2") (pintype "passive"))
      (node (ref "C30") (pin "2") (pinfunction "2_2") (pintype "passive"))
      (node (ref "C31") (pin "2") (pinfunction "2_2") (pintype "passive"))
      (node (ref "C32") (pin "2") (pinfunction "2_2") (pintype "passive"))
      (node (ref "C33") (pin "2") (pinfunction "2_2") (pintype "passive"))
      (node (ref "C34") (pin "2") (pinfunction "2_2") (pintype "passive"))
      (node (ref "U1") (pin "AA23") (pinfunction "VDD_MAIN_11_AA23") (pintype "passive"))
      (node (ref "U1") (pin "AC17") (pinfunction "VDD_MAIN_12_AC17") (pintype "passive"))
      (node (ref "U1") (pin "AC19") (pinfunction "VDD_MAIN_13_AC19") (pintype "passive"))
      (node (ref "U1") (pin "AC21") (pinfunction "VDD_MAIN_14_AC21") (pintype "passive"))
      (node (ref "U1") (pin "AC23") (pinfunction "VDD_MAIN_15_AC23") (pintype "passive"))
      (node (ref "U1") (pin "N15") (pinfunction "VDD_MAIN_1_N15") (pintype "passive"))
      (node (ref "U1") (pin "N17") (pinfunction "VDD_MAIN_2_N17") (pintype "passive"))
      (node (ref "U1") (pin "N19") (pinfunction "VDD_MAIN_3_N19") (pintype "passive"))
      (node (ref "U1") (pin "N21") (pinfunction "VDD_MAIN_4_N21") (pintype "passive"))
      (node (ref "U1") (pin "N23") (pinfunction "VDD_MAIN_5_N23") (pintype "passive"))
      (node (ref "U1") (pin "R15") (pinfunction "VDD_MAIN_6_R15") (pintype "passive"))
      (node (ref "U1") (pin "R17") (pinfunction "VDD_MAIN_7_R17") (pintype "passive"))
      (node (ref "U1") (pin "R23") (pinfunction "VDD_MAIN_8_R23") (pintype "passive"))
      (node (ref "U1") (pin "U23") (pinfunction "VDD_MAIN_9_U23") (pintype "passive"))
      (node (ref "U1") (pin "W23") (pinfunction "VDD_MAIN_10_W23") (pintype "passive"))
    )
    (net (code "7") (name "VDD_MEMC") (class "Default")
      (node (ref "C1") (pin "2") (pinfunction "2_2") (pintype "passive"))
      (node (ref "C10") (pin "2") (pinfunction "2_2") (pintype "passive"))
      (node (ref "C11") (pin "2") (pinfunction "2_2") (pintype "passive"))
      (node (ref "C2") (pin "2") (pinfunction "2_2") (pintype "passive"))
      (node (ref "C3") (pin "2") (pinfunction "2_2") (pintype "passive"))
      (node (ref "C35") (pin "2") (pinfunction "2_2") (pintype "passive"))
      (node (ref "C36") (pin "2") (pinfunction "2_2") (pintype "passive"))
      (node (ref "C37") (pin "2") (pinfunction "2_2") (pintype "passive"))
      (node (ref "C38") (pin "2") (pinfunction "2_2") (pintype "passive"))
      (node (ref "C4") (pin "2") (pinfunction "2_2") (pintype "passive"))
      (node (ref "C5") (pin "2") (pinfunction "2_2") (pintype "passive"))
      (node (ref "C6") (pin "2") (pinfunction "2_2") (pintype "passive"))
      (node (ref "C7") (pin "2") (pinfunction "2_2") (pintype "passive"))
      (node (ref "C8") (pin "2") (pinfunction "2_2") (pintype "passive"))
      (node (ref "C9") (pin "2") (pinfunction "2_2") (pintype "passive"))
      (node (ref "U1") (pin "AA13") (pinfunction "VDD_MEMC_9_AA13") (pintype "passive"))
      (node (ref "U1") (pin "AC13") (pinfunction "VDD_MEMC_10_AC13") (pintype "passive"))
      (node (ref "U1") (pin "AC15") (pinfunction "VDD_MEMC_11_AC15") (pintype "passive"))
      (node (ref "U1") (pin "N13") (pinfunction "VDD_MEMC_1_N13") (pintype "passive"))
      (node (ref "U1") (pin "R13") (pinfunction "VDD_MEMC_2_R13") (pintype "passive"))
      (node (ref "U1") (pin "U13") (pinfunction "VDD_MEMC_3_U13") (pintype "passive"))
      (node (ref "U1") (pin "U19") (pinfunction "VDD_MEMC_4_U19") (pintype "passive"))
      (node (ref "U1") (pin "W13") (pinfunction "VDD_MEMC_5_W13") (pintype "passive"))
      (node (ref "U1") (pin "W15") (pinfunction "VDD_MEMC_6_W15") (pintype "passive"))
      (node (ref "U1") (pin "W17") (pinfunction "VDD_MEMC_7_W17") (pintype "passive"))
      (node (ref "U1") (pin "W19") (pinfunction "VDD_MEMC_8_W19") (pintype "passive"))
    )
  )
)
